# hover_controller_v3.net
KiCad netlist of a schematic drawn in EAGLE
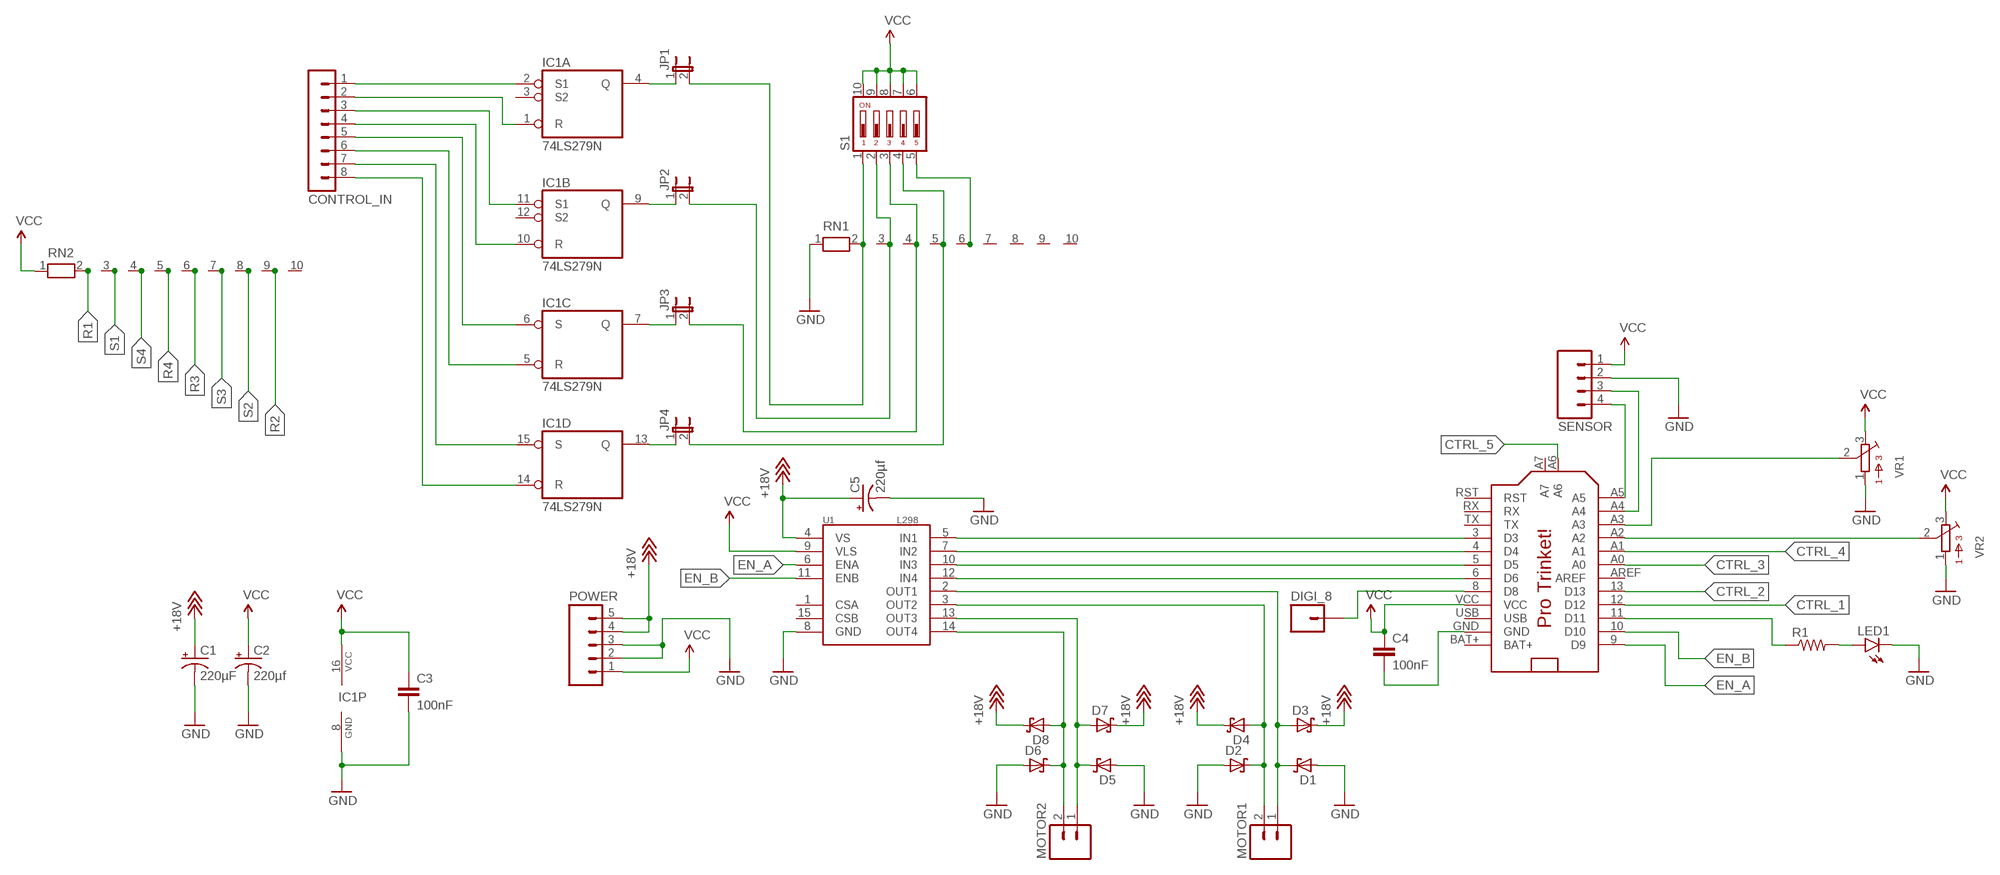
[diagram p0: schematic, sheet 1]

(export (version "E")
  (design (tool "Eeschema 10.0.6"))
  (components
    (comp (ref "C1")
      (value "220µF")
      (footprint "eagle-import:CPOL-RADIAL-10UF-25V")
      (libsource (lib "eagle-import") (part "CAP_POLPTH2"))
    )
    (comp (ref "C2")
      (value "220µf")
      (footprint "eagle-import:CPOL-RADIAL-10UF-25V")
      (libsource (lib "eagle-import") (part "CAP_POLPTH2"))
    )
    (comp (ref "C3")
      (value "100nF")
      (footprint "eagle-import:CAP-PTH-5MM")
      (libsource (lib "eagle-import") (part "CAPPTH1"))
    )
    (comp (ref "C4")
      (value "100nF")
      (footprint "eagle-import:CAP-PTH-5MM")
      (libsource (lib "eagle-import") (part "CAPPTH1"))
    )
    (comp (ref "C5")
      (value "220µf")
      (footprint "eagle-import:CPOL-RADIAL-10UF-25V")
      (libsource (lib "eagle-import") (part "CAP_POLPTH2"))
    )
    (comp (ref "CONTROL_IN")
      (value "MA08-1")
      (footprint "eagle-import:MA08-1")
      (libsource (lib "eagle-import") (part "MA08-1"))
    )
    (comp (ref "D1")
      (value "SCHOTTKY-DIODEDO35-7")
      (footprint "eagle-import:DO35-7")
      (libsource (lib "eagle-import") (part "SCHOTTKY-DIODEDO35-7"))
    )
    (comp (ref "D2")
      (value "SCHOTTKY-DIODEDO35-7")
      (footprint "eagle-import:DO35-7")
      (libsource (lib "eagle-import") (part "SCHOTTKY-DIODEDO35-7"))
    )
    (comp (ref "D3")
      (value "SCHOTTKY-DIODEDO35-7")
      (footprint "eagle-import:DO35-7")
      (libsource (lib "eagle-import") (part "SCHOTTKY-DIODEDO35-7"))
    )
    (comp (ref "D4")
      (value "SCHOTTKY-DIODEDO35-7")
      (footprint "eagle-import:DO35-7")
      (libsource (lib "eagle-import") (part "SCHOTTKY-DIODEDO35-7"))
    )
    (comp (ref "D5")
      (value "SCHOTTKY-DIODEDO35-7")
      (footprint "eagle-import:DO35-7")
      (libsource (lib "eagle-import") (part "SCHOTTKY-DIODEDO35-7"))
    )
    (comp (ref "D6")
      (value "SCHOTTKY-DIODEDO35-7")
      (footprint "eagle-import:DO35-7")
      (libsource (lib "eagle-import") (part "SCHOTTKY-DIODEDO35-7"))
    )
    (comp (ref "D7")
      (value "SCHOTTKY-DIODEDO35-7")
      (footprint "eagle-import:DO35-7")
      (libsource (lib "eagle-import") (part "SCHOTTKY-DIODEDO35-7"))
    )
    (comp (ref "D8")
      (value "SCHOTTKY-DIODEDO35-7")
      (footprint "eagle-import:DO35-7")
      (libsource (lib "eagle-import") (part "SCHOTTKY-DIODEDO35-7"))
    )
    (comp (ref "DIGI_8")
      (value "M01PTH")
      (footprint "eagle-import:1X01")
      (libsource (lib "eagle-import") (part "M01PTH"))
    )
    (comp (ref "IC1")
      (value "74LS279N")
      (footprint "eagle-import:DIL16")
      (libsource (lib "eagle-import") (part "74279NLS"))
    )
    (comp (ref "JP1")
      (value "JUMPER-2PTH")
      (footprint "eagle-import:1X02")
      (libsource (lib "eagle-import") (part "JUMPER-2PTH"))
    )
    (comp (ref "JP2")
      (value "JUMPER-2PTH")
      (footprint "eagle-import:1X02")
      (libsource (lib "eagle-import") (part "JUMPER-2PTH"))
    )
    (comp (ref "JP3")
      (value "JUMPER-2PTH")
      (footprint "eagle-import:1X02")
      (libsource (lib "eagle-import") (part "JUMPER-2PTH"))
    )
    (comp (ref "JP4")
      (value "JUMPER-2PTH")
      (footprint "eagle-import:1X02")
      (libsource (lib "eagle-import") (part "JUMPER-2PTH"))
    )
    (comp (ref "LED1")
      (value "LED-3MM-NO_SILK")
      (footprint "eagle-import:LED3MM-NS")
      (libsource (lib "eagle-import") (part "LED-3MM-NO_SILK"))
    )
    (comp (ref "MOTOR1")
      (value "M02PTH")
      (footprint "eagle-import:1X02")
      (libsource (lib "eagle-import") (part "M02PTH"))
    )
    (comp (ref "MOTOR2")
      (value "M02PTH")
      (footprint "eagle-import:1X02")
      (libsource (lib "eagle-import") (part "M02PTH"))
    )
    (comp (ref "POWER")
      (value "M05JST-VERT")
      (footprint "eagle-import:JST-5-PTH-VERT")
      (libsource (lib "eagle-import") (part "M05JST-VERT"))
    )
    (comp (ref "R1")
      (value "RESISTORPTH-1/4W")
      (footprint "eagle-import:AXIAL-0.4")
      (libsource (lib "eagle-import") (part "RESISTORPTH-1/4W"))
    )
    (comp (ref "RN1")
      (value "RN09")
      (footprint "eagle-import:RN-10")
      (libsource (lib "eagle-import") (part "RN09"))
    )
    (comp (ref "RN2")
      (value "RN09")
      (footprint "eagle-import:RN-10")
      (libsource (lib "eagle-import") (part "RN09"))
    )
    (comp (ref "S1")
      (value "DIP05YL")
      (footprint "eagle-import:DIP05YL")
      (libsource (lib "eagle-import") (part "DIP05YL"))
    )
    (comp (ref "SENSOR")
      (value "M04PTH")
      (footprint "eagle-import:1X04")
      (libsource (lib "eagle-import") (part "M04PTH"))
    )
    (comp (ref "U$1")
      (value "PRO_TRINKET")
      (footprint "eagle-import:PROTRINKET")
      (libsource (lib "eagle-import") (part "PRO_TRINKET"))
    )
    (comp (ref "U1")
      (value "L298")
      (footprint "eagle-import:MULTIWATT15")
      (libsource (lib "eagle-import") (part "L298"))
    )
    (comp (ref "VR1")
      (value "BOURNS_3362P_TRIMMERP")
      (footprint "eagle-import:BOURNS_3362P_TRIMMER")
      (libsource (lib "eagle-import") (part "BOURNS_3362P_TRIMMERP"))
    )
    (comp (ref "VR2")
      (value "BOURNS_3362P_TRIMMERP")
      (footprint "eagle-import:BOURNS_3362P_TRIMMER")
      (libsource (lib "eagle-import") (part "BOURNS_3362P_TRIMMERP"))
    )
  )
  (nets
    (net (code "1") (name "+18V") (class "Default")
      (node (ref "C1") (pin "1") (pinfunction "+_1") (pintype "passive"))
      (node (ref "C5") (pin "1") (pinfunction "+_1") (pintype "passive"))
      (node (ref "D3") (pin "C") (pinfunction "C_C") (pintype "passive"))
      (node (ref "D4") (pin "C") (pinfunction "C_C") (pintype "passive"))
      (node (ref "D7") (pin "C") (pinfunction "C_C") (pintype "passive"))
      (node (ref "D8") (pin "C") (pinfunction "C_C") (pintype "passive"))
      (node (ref "POWER") (pin "4") (pinfunction "4_4") (pintype "passive"))
      (node (ref "POWER") (pin "5") (pinfunction "5_5") (pintype "passive"))
      (node (ref "U1") (pin "4") (pinfunction "VS_4") (pintype "bidirectional"))
    )
    (net (code "2") (name "/BAT+") (class "Default")
      (node (ref "U$1") (pin "BAT+") (pinfunction "BAT+_BAT+") (pintype "power_in"))
    )
    (net (code "3") (name "/USB") (class "Default")
      (node (ref "U$1") (pin "USB") (pinfunction "USB_USB") (pintype "power_in"))
    )
    (net (code "4") (name "CTRL_1") (class "Default")
      (node (ref "JP1") (pin "2") (pinfunction "2_2") (pintype "passive"))
      (node (ref "RN1") (pin "2") (pinfunction "2_2") (pintype "passive"))
      (node (ref "S1") (pin "1") (pinfunction "1_1") (pintype "passive"))
      (node (ref "U$1") (pin "12") (pinfunction "D12_12") (pintype "bidirectional"))
    )
    (net (code "5") (name "CTRL_2") (class "Default")
      (node (ref "JP2") (pin "2") (pinfunction "2_2") (pintype "passive"))
      (node (ref "RN1") (pin "3") (pinfunction "3_3") (pintype "passive"))
      (node (ref "S1") (pin "2") (pinfunction "2_2") (pintype "passive"))
      (node (ref "U$1") (pin "13") (pinfunction "D13_13") (pintype "bidirectional"))
    )
    (net (code "6") (name "CTRL_3") (class "Default")
      (node (ref "JP3") (pin "2") (pinfunction "2_2") (pintype "passive"))
      (node (ref "RN1") (pin "4") (pinfunction "4_4") (pintype "passive"))
      (node (ref "S1") (pin "3") (pinfunction "3_3") (pintype "passive"))
      (node (ref "U$1") (pin "A0") (pinfunction "A0_A0") (pintype "bidirectional"))
    )
    (net (code "7") (name "CTRL_4") (class "Default")
      (node (ref "JP4") (pin "2") (pinfunction "2_2") (pintype "passive"))
      (node (ref "RN1") (pin "5") (pinfunction "5_5") (pintype "passive"))
      (node (ref "S1") (pin "4") (pinfunction "4_4") (pintype "passive"))
      (node (ref "U$1") (pin "A1") (pinfunction "A1_A1") (pintype "bidirectional"))
    )
    (net (code "8") (name "CTRL_5") (class "Default")
      (node (ref "RN1") (pin "6") (pinfunction "6_6") (pintype "passive"))
      (node (ref "S1") (pin "5") (pinfunction "5_5") (pintype "passive"))
      (node (ref "U$1") (pin "A6") (pinfunction "A6_A6") (pintype "passive"))
    )
    (net (code "9") (name "EN_A") (class "Default")
      (node (ref "U$1") (pin "9") (pinfunction "D9_9") (pintype "bidirectional"))
      (node (ref "U1") (pin "6") (pinfunction "ENA_6") (pintype "bidirectional"))
    )
    (net (code "10") (name "EN_B") (class "Default")
      (node (ref "U$1") (pin "10") (pinfunction "D10_10") (pintype "bidirectional"))
      (node (ref "U1") (pin "11") (pinfunction "ENB_11") (pintype "bidirectional"))
    )
    (net (code "11") (name "GND") (class "Default")
      (node (ref "C1") (pin "2") (pinfunction "-_2") (pintype "passive"))
      (node (ref "C2") (pin "2") (pinfunction "-_2") (pintype "passive"))
      (node (ref "C3") (pin "2") (pinfunction "2_2") (pintype "passive"))
      (node (ref "C5") (pin "2") (pinfunction "-_2") (pintype "passive"))
      (node (ref "D1") (pin "A") (pinfunction "A_A") (pintype "passive"))
      (node (ref "D2") (pin "A") (pinfunction "A_A") (pintype "passive"))
      (node (ref "D5") (pin "A") (pinfunction "A_A") (pintype "passive"))
      (node (ref "D6") (pin "A") (pinfunction "A_A") (pintype "passive"))
      (node (ref "IC1") (pin "8") (pinfunction "GND_8") (pintype "power_in"))
      (node (ref "LED1") (pin "K") (pinfunction "C_K") (pintype "passive"))
      (node (ref "POWER") (pin "2") (pinfunction "2_2") (pintype "passive"))
      (node (ref "POWER") (pin "3") (pinfunction "3_3") (pintype "passive"))
      (node (ref "RN1") (pin "1") (pinfunction "1_1") (pintype "passive"))
      (node (ref "SENSOR") (pin "2") (pinfunction "2_2") (pintype "passive"))
      (node (ref "U1") (pin "8") (pinfunction "GND_8") (pintype "bidirectional"))
      (node (ref "VR1") (pin "1") (pinfunction "1_1") (pintype "passive"))
      (node (ref "VR2") (pin "1") (pinfunction "1_1") (pintype "passive"))
    )
    (net (code "12") (name "Net-(C4-Pad2)") (class "Default")
      (node (ref "C4") (pin "2") (pinfunction "2_2") (pintype "passive"))
      (node (ref "U$1") (pin "GND") (pinfunction "GND_GND") (pintype "power_in"))
    )
    (net (code "13") (name "Net-(IC1A-Q)") (class "Default")
      (node (ref "IC1") (pin "4") (pinfunction "Q_4") (pintype "output"))
      (node (ref "JP1") (pin "1") (pinfunction "1_1") (pintype "passive"))
    )
    (net (code "14") (name "Net-(IC1B-Q)") (class "Default")
      (node (ref "IC1") (pin "9") (pinfunction "Q_9") (pintype "output"))
      (node (ref "JP2") (pin "1") (pinfunction "1_1") (pintype "passive"))
    )
    (net (code "15") (name "Net-(IC1C-Q)") (class "Default")
      (node (ref "IC1") (pin "7") (pinfunction "Q_7") (pintype "output"))
      (node (ref "JP3") (pin "1") (pinfunction "1_1") (pintype "passive"))
    )
    (net (code "16") (name "Net-(IC1D-Q)") (class "Default")
      (node (ref "IC1") (pin "13") (pinfunction "Q_13") (pintype "output"))
      (node (ref "JP4") (pin "1") (pinfunction "1_1") (pintype "passive"))
    )
    (net (code "17") (name "Net-(R1-1)") (class "Default")
      (node (ref "R1") (pin "P$1") (pinfunction "1_P$1") (pintype "passive"))
      (node (ref "U$1") (pin "11") (pinfunction "D11_11") (pintype "bidirectional"))
    )
    (net (code "18") (name "Net-(R1-2)") (class "Default")
      (node (ref "LED1") (pin "A") (pinfunction "A_A") (pintype "passive"))
      (node (ref "R1") (pin "P$2") (pinfunction "2_P$2") (pintype "passive"))
    )
    (net (code "19") (name "Net-(SENSOR-Pad3)") (class "Default")
      (node (ref "SENSOR") (pin "3") (pinfunction "3_3") (pintype "passive"))
      (node (ref "U$1") (pin "A4") (pinfunction "A4_A4") (pintype "bidirectional"))
    )
    (net (code "20") (name "Net-(SENSOR-Pad4)") (class "Default")
      (node (ref "SENSOR") (pin "4") (pinfunction "4_4") (pintype "passive"))
      (node (ref "U$1") (pin "A5") (pinfunction "A5_A5") (pintype "bidirectional"))
    )
    (net (code "21") (name "Net-(U$1-D3)") (class "Default")
      (node (ref "U$1") (pin "3") (pinfunction "D3_3") (pintype "bidirectional"))
      (node (ref "U1") (pin "5") (pinfunction "IN1_5") (pintype "bidirectional"))
    )
    (net (code "22") (name "Net-(U$1-D4)") (class "Default")
      (node (ref "U$1") (pin "4") (pinfunction "D4_4") (pintype "bidirectional"))
      (node (ref "U1") (pin "7") (pinfunction "IN2_7") (pintype "bidirectional"))
    )
    (net (code "23") (name "Net-(U$1-D5)") (class "Default")
      (node (ref "U$1") (pin "5") (pinfunction "D5_5") (pintype "bidirectional"))
      (node (ref "U1") (pin "10") (pinfunction "IN3_10") (pintype "bidirectional"))
    )
    (net (code "24") (name "Net-(U$1-D6)") (class "Default")
      (node (ref "U$1") (pin "6") (pinfunction "D6_6") (pintype "bidirectional"))
      (node (ref "U1") (pin "12") (pinfunction "IN4_12") (pintype "bidirectional"))
    )
    (net (code "25") (name "Net-(U$1-D8)") (class "Default")
      (node (ref "DIGI_8") (pin "1") (pinfunction "1_1") (pintype "passive"))
      (node (ref "U$1") (pin "8") (pinfunction "D8_8") (pintype "bidirectional"))
    )
    (net (code "26") (name "Net-(U$1-PadA2)") (class "Default")
      (node (ref "U$1") (pin "A2") (pinfunction "A2_A2") (pintype "bidirectional"))
      (node (ref "VR2") (pin "2") (pinfunction "2_2") (pintype "passive"))
    )
    (net (code "27") (name "Net-(U$1-PadA3)") (class "Default")
      (node (ref "U$1") (pin "A3") (pinfunction "A3_A3") (pintype "bidirectional"))
      (node (ref "VR1") (pin "2") (pinfunction "2_2") (pintype "passive"))
    )
    (net (code "28") (name "Net-(U1-OUT1)") (class "Default")
      (node (ref "D1") (pin "C") (pinfunction "C_C") (pintype "passive"))
      (node (ref "D3") (pin "A") (pinfunction "A_A") (pintype "passive"))
      (node (ref "MOTOR1") (pin "1") (pinfunction "1_1") (pintype "passive"))
      (node (ref "U1") (pin "2") (pinfunction "OUT1_2") (pintype "bidirectional"))
    )
    (net (code "29") (name "Net-(U1-OUT2)") (class "Default")
      (node (ref "D2") (pin "C") (pinfunction "C_C") (pintype "passive"))
      (node (ref "D4") (pin "A") (pinfunction "A_A") (pintype "passive"))
      (node (ref "MOTOR1") (pin "2") (pinfunction "2_2") (pintype "passive"))
      (node (ref "U1") (pin "3") (pinfunction "OUT2_3") (pintype "bidirectional"))
    )
    (net (code "30") (name "Net-(U1-OUT3)") (class "Default")
      (node (ref "D5") (pin "C") (pinfunction "C_C") (pintype "passive"))
      (node (ref "D7") (pin "A") (pinfunction "A_A") (pintype "passive"))
      (node (ref "MOTOR2") (pin "1") (pinfunction "1_1") (pintype "passive"))
      (node (ref "U1") (pin "13") (pinfunction "OUT3_13") (pintype "bidirectional"))
    )
    (net (code "31") (name "Net-(U1-OUT4)") (class "Default")
      (node (ref "D6") (pin "C") (pinfunction "C_C") (pintype "passive"))
      (node (ref "D8") (pin "A") (pinfunction "A_A") (pintype "passive"))
      (node (ref "MOTOR2") (pin "2") (pinfunction "2_2") (pintype "passive"))
      (node (ref "U1") (pin "14") (pinfunction "OUT4_14") (pintype "bidirectional"))
    )
    (net (code "32") (name "R1") (class "Default")
      (node (ref "CONTROL_IN") (pin "2") (pinfunction "2_2") (pintype "passive"))
      (node (ref "IC1") (pin "1") (pinfunction "R_1") (pintype "input"))
      (node (ref "RN2") (pin "2") (pinfunction "2_2") (pintype "passive"))
    )
    (net (code "33") (name "R2") (class "Default")
      (node (ref "CONTROL_IN") (pin "4") (pinfunction "4_4") (pintype "passive"))
      (node (ref "IC1") (pin "10") (pinfunction "R_10") (pintype "input"))
      (node (ref "RN2") (pin "9") (pinfunction "9_9") (pintype "passive"))
    )
    (net (code "34") (name "R3") (class "Default")
      (node (ref "CONTROL_IN") (pin "6") (pinfunction "6_6") (pintype "passive"))
      (node (ref "IC1") (pin "5") (pinfunction "R_5") (pintype "input"))
      (node (ref "RN2") (pin "6") (pinfunction "6_6") (pintype "passive"))
    )
    (net (code "35") (name "R4") (class "Default")
      (node (ref "CONTROL_IN") (pin "8") (pinfunction "8_8") (pintype "passive"))
      (node (ref "IC1") (pin "14") (pinfunction "R_14") (pintype "input"))
      (node (ref "RN2") (pin "5") (pinfunction "5_5") (pintype "passive"))
    )
    (net (code "36") (name "S1") (class "Default")
      (node (ref "CONTROL_IN") (pin "1") (pinfunction "1_1") (pintype "passive"))
      (node (ref "IC1") (pin "2") (pinfunction "S1_2") (pintype "input"))
      (node (ref "RN2") (pin "3") (pinfunction "3_3") (pintype "passive"))
    )
    (net (code "37") (name "S2") (class "Default")
      (node (ref "CONTROL_IN") (pin "3") (pinfunction "3_3") (pintype "passive"))
      (node (ref "IC1") (pin "11") (pinfunction "S1_11") (pintype "input"))
      (node (ref "RN2") (pin "8") (pinfunction "8_8") (pintype "passive"))
    )
    (net (code "38") (name "S3") (class "Default")
      (node (ref "CONTROL_IN") (pin "5") (pinfunction "5_5") (pintype "passive"))
      (node (ref "IC1") (pin "6") (pinfunction "S_6") (pintype "input"))
      (node (ref "RN2") (pin "7") (pinfunction "7_7") (pintype "passive"))
    )
    (net (code "39") (name "S4") (class "Default")
      (node (ref "CONTROL_IN") (pin "7") (pinfunction "7_7") (pintype "passive"))
      (node (ref "IC1") (pin "15") (pinfunction "S_15") (pintype "input"))
      (node (ref "RN2") (pin "4") (pinfunction "4_4") (pintype "passive"))
    )
    (net (code "40") (name "VCC") (class "Default")
      (node (ref "C2") (pin "1") (pinfunction "+_1") (pintype "passive"))
      (node (ref "C3") (pin "1") (pinfunction "1_1") (pintype "passive"))
      (node (ref "C4") (pin "1") (pinfunction "1_1") (pintype "passive"))
      (node (ref "IC1") (pin "16") (pinfunction "VCC_16") (pintype "power_in"))
      (node (ref "POWER") (pin "1") (pinfunction "1_1") (pintype "passive"))
      (node (ref "RN2") (pin "1") (pinfunction "1_1") (pintype "passive"))
      (node (ref "S1") (pin "10") (pinfunction "10_10") (pintype "passive"))
      (node (ref "S1") (pin "6") (pinfunction "6_6") (pintype "passive"))
      (node (ref "S1") (pin "7") (pinfunction "7_7") (pintype "passive"))
      (node (ref "S1") (pin "8") (pinfunction "8_8") (pintype "passive"))
      (node (ref "S1") (pin "9") (pinfunction "9_9") (pintype "passive"))
      (node (ref "SENSOR") (pin "1") (pinfunction "1_1") (pintype "passive"))
      (node (ref "U$1") (pin "VCC") (pinfunction "VCC_VCC") (pintype "power_in"))
      (node (ref "U1") (pin "9") (pinfunction "VLS_9") (pintype "bidirectional"))
      (node (ref "VR1") (pin "3") (pinfunction "3_3") (pintype "passive"))
      (node (ref "VR2") (pin "3") (pinfunction "3_3") (pintype "passive"))
    )
    (net (code "41") (name "unconnected-(IC1A-S2-Pad3)") (class "Default")
      (node (ref "IC1") (pin "3") (pinfunction "S2_3") (pintype "input"))
    )
    (net (code "42") (name "unconnected-(IC1B-S2-Pad12)") (class "Default")
      (node (ref "IC1") (pin "12") (pinfunction "S2_12") (pintype "input"))
    )
    (net (code "43") (name "unconnected-(RN1-Pad7)") (class "Default")
      (node (ref "RN1") (pin "7") (pinfunction "7_7") (pintype "passive"))
    )
    (net (code "44") (name "unconnected-(RN1-Pad8)") (class "Default")
      (node (ref "RN1") (pin "8") (pinfunction "8_8") (pintype "passive"))
    )
    (net (code "45") (name "unconnected-(RN1-Pad9)") (class "Default")
      (node (ref "RN1") (pin "9") (pinfunction "9_9") (pintype "passive"))
    )
    (net (code "46") (name "unconnected-(RN1-Pad10)") (class "Default")
      (node (ref "RN1") (pin "10") (pinfunction "10_10") (pintype "passive"))
    )
    (net (code "47") (name "unconnected-(RN2-Pad10)") (class "Default")
      (node (ref "RN2") (pin "10") (pinfunction "10_10") (pintype "passive"))
    )
    (net (code "48") (name "unconnected-(U$1-PadA7)") (class "Default")
      (node (ref "U$1") (pin "A7") (pinfunction "A7_A7") (pintype "passive"))
    )
    (net (code "49") (name "unconnected-(U$1-PadAREF)") (class "Default")
      (node (ref "U$1") (pin "AREF") (pinfunction "AREF_AREF") (pintype "passive"))
    )
    (net (code "50") (name "unconnected-(U$1-PadRST)") (class "Default")
      (node (ref "U$1") (pin "RST") (pinfunction "RST_RST") (pintype "passive"))
    )
    (net (code "51") (name "unconnected-(U$1-PadRX)") (class "Default")
      (node (ref "U$1") (pin "RX") (pinfunction "RX_RX") (pintype "bidirectional"))
    )
    (net (code "52") (name "unconnected-(U$1-PadTX)") (class "Default")
      (node (ref "U$1") (pin "TX") (pinfunction "TX_TX") (pintype "bidirectional"))
    )
    (net (code "53") (name "unconnected-(U1-CSA-Pad1)") (class "Default")
      (node (ref "U1") (pin "1") (pinfunction "CSA_1") (pintype "bidirectional"))
    )
    (net (code "54") (name "unconnected-(U1-CSB-Pad15)") (class "Default")
      (node (ref "U1") (pin "15") (pinfunction "CSB_15") (pintype "bidirectional"))
    )
  )
)
